# ltc3886_breadboardbreakout.net
KiCad netlist of a schematic drawn in EAGLE
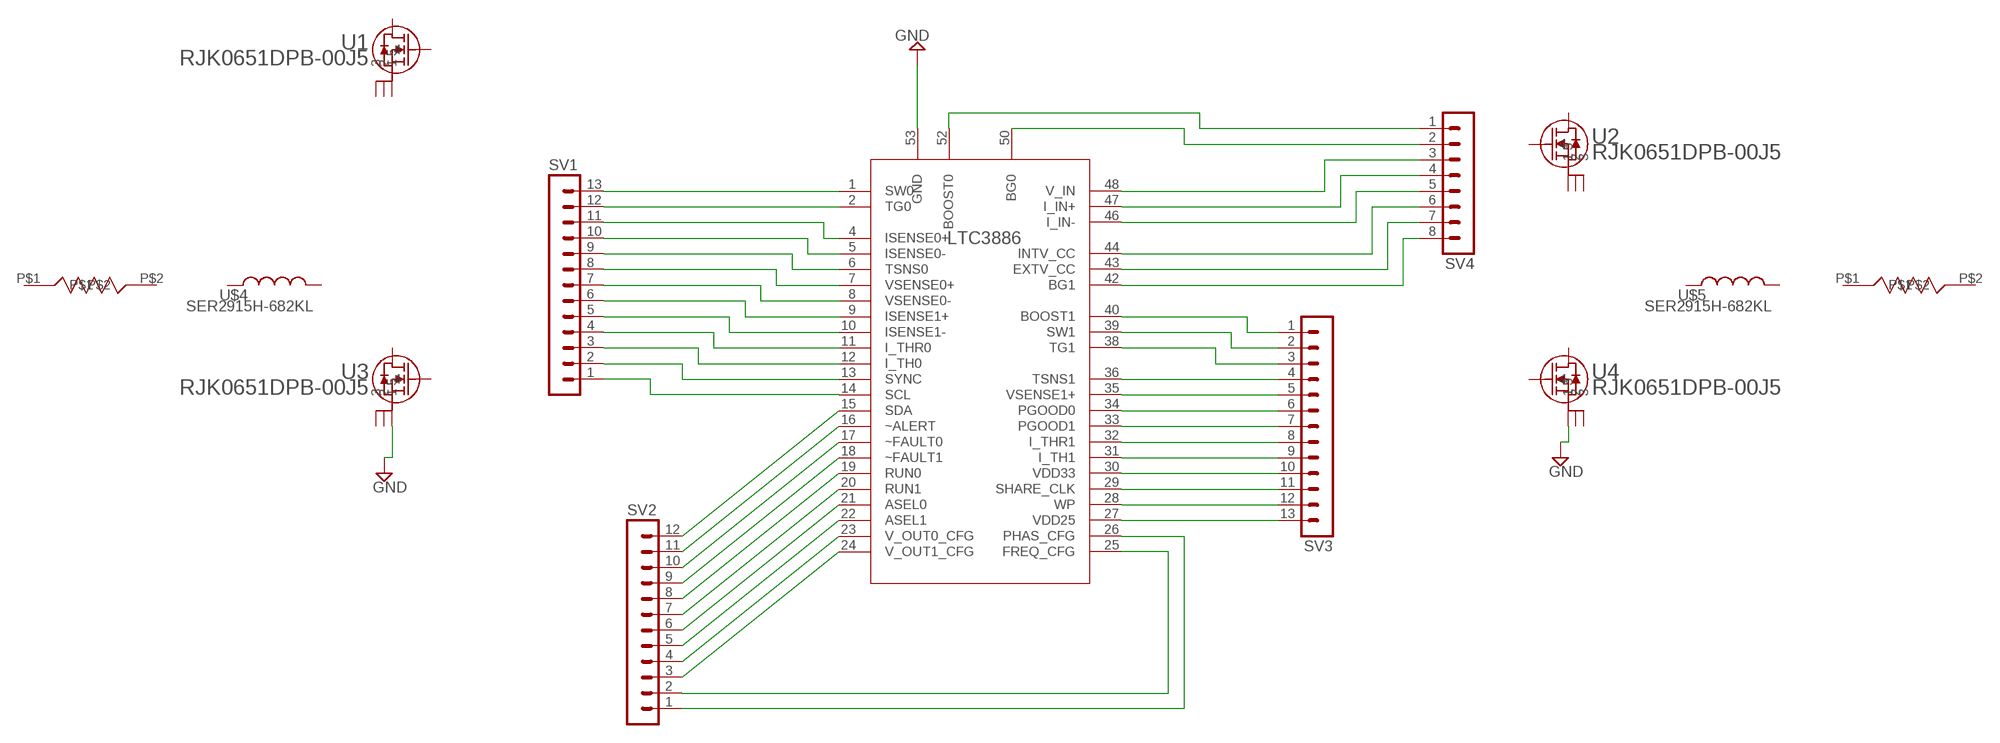
[diagram p0: schematic, sheet 1]

(export (version "E")
  (design (tool "Eeschema 10.0.6"))
  (components
    (comp (ref "GND")
      (value "LTC3886")
      (footprint "eagle-import:QFN-52_UKG_2")
      (libsource (lib "eagle-import") (part "LTC3886"))
    )
    (comp (ref "SV1")
      (value "MA13-1")
      (footprint "eagle-import:MA13-1")
      (libsource (lib "eagle-import") (part "MA13-1"))
    )
    (comp (ref "SV2")
      (value "MA12-1")
      (footprint "eagle-import:MA12-1")
      (libsource (lib "eagle-import") (part "MA12-1"))
    )
    (comp (ref "SV3")
      (value "MA13-1")
      (footprint "eagle-import:MA13-1")
      (libsource (lib "eagle-import") (part "MA13-1"))
    )
    (comp (ref "SV4")
      (value "MA08-1")
      (footprint "eagle-import:MA08-1")
      (libsource (lib "eagle-import") (part "MA08-1"))
    )
    (comp (ref "U$2")
      (value "CSS2H-2512K-2L00FE")
      (footprint "eagle-import:CSS2H-2512K-2L00FE")
      (libsource (lib "eagle-import") (part "CSS2H-2512K-2L00FE"))
    )
    (comp (ref "U$3")
      (value "CSS2H-2512K-2L00FE")
      (footprint "eagle-import:CSS2H-2512K-2L00FE")
      (libsource (lib "eagle-import") (part "CSS2H-2512K-2L00FE"))
    )
    (comp (ref "U$4")
      (value "SER2915H-682KL")
      (footprint "eagle-import:SER2915H-682KL")
      (libsource (lib "eagle-import") (part "SER2915H-682KL"))
    )
    (comp (ref "U$5")
      (value "SER2915H-682KL")
      (footprint "eagle-import:SER2915H-682KL")
      (libsource (lib "eagle-import") (part "SER2915H-682KL"))
    )
    (comp (ref "U1")
      (value "RJK0651DPB-00J5")
      (footprint "eagle-import:LFPAK")
      (fields (field (name "MANUFACTURER_PART_NUMBER") "RJK0651DPB00#J5"))
      (libsource (lib "eagle-import") (part "RJK0651DPB-00J5"))
    )
    (comp (ref "U2")
      (value "RJK0651DPB-00J5")
      (footprint "eagle-import:LFPAK")
      (fields (field (name "MANUFACTURER_PART_NUMBER") "RJK0651DPB00#J5"))
      (libsource (lib "eagle-import") (part "RJK0651DPB-00J5"))
    )
    (comp (ref "U3")
      (value "RJK0651DPB-00J5")
      (footprint "eagle-import:LFPAK")
      (fields (field (name "MANUFACTURER_PART_NUMBER") "RJK0651DPB00#J5"))
      (libsource (lib "eagle-import") (part "RJK0651DPB-00J5"))
    )
    (comp (ref "U4")
      (value "RJK0651DPB-00J5")
      (footprint "eagle-import:LFPAK")
      (fields (field (name "MANUFACTURER_PART_NUMBER") "RJK0651DPB00#J5"))
      (libsource (lib "eagle-import") (part "RJK0651DPB-00J5"))
    )
  )
  (nets
    (net (code "1") (name "GND") (class "Default")
      (node (ref "GND") (pin "53") (pinfunction "GND_53") (pintype "bidirectional"))
      (node (ref "U3") (pin "1") (pinfunction "1_1") (pintype "passive"))
      (node (ref "U4") (pin "1") (pinfunction "1_1") (pintype "passive"))
    )
    (net (code "2") (name "Net-(GND-ASEL0)") (class "Default")
      (node (ref "GND") (pin "21") (pinfunction "ASEL0_21") (pintype "passive"))
      (node (ref "SV2") (pin "6") (pinfunction "6_6") (pintype "passive"))
    )
    (net (code "3") (name "Net-(GND-ASEL1)") (class "Default")
      (node (ref "GND") (pin "22") (pinfunction "ASEL1_22") (pintype "passive"))
      (node (ref "SV2") (pin "5") (pinfunction "5_5") (pintype "passive"))
    )
    (net (code "4") (name "Net-(GND-BG0)") (class "Default")
      (node (ref "GND") (pin "50") (pinfunction "BG0_50") (pintype "bidirectional"))
      (node (ref "SV4") (pin "2") (pinfunction "2_2") (pintype "passive"))
    )
    (net (code "5") (name "Net-(GND-BG1)") (class "Default")
      (node (ref "GND") (pin "42") (pinfunction "BG1_42") (pintype "passive"))
      (node (ref "SV4") (pin "8") (pinfunction "8_8") (pintype "passive"))
    )
    (net (code "6") (name "Net-(GND-BOOST0)") (class "Default")
      (node (ref "GND") (pin "52") (pinfunction "BOOST0_52") (pintype "bidirectional"))
      (node (ref "SV4") (pin "1") (pinfunction "1_1") (pintype "passive"))
    )
    (net (code "7") (name "Net-(GND-BOOST1)") (class "Default")
      (node (ref "GND") (pin "40") (pinfunction "BOOST1_40") (pintype "passive"))
      (node (ref "SV3") (pin "1") (pinfunction "1_1") (pintype "passive"))
    )
    (net (code "8") (name "Net-(GND-EXTV_CC)") (class "Default")
      (node (ref "GND") (pin "43") (pinfunction "EXTV_CC_43") (pintype "passive"))
      (node (ref "SV4") (pin "7") (pinfunction "7_7") (pintype "passive"))
    )
    (net (code "9") (name "Net-(GND-FREQ_CFG)") (class "Default")
      (node (ref "GND") (pin "25") (pinfunction "FREQ_CFG_25") (pintype "passive"))
      (node (ref "SV2") (pin "2") (pinfunction "2_2") (pintype "passive"))
    )
    (net (code "10") (name "Net-(GND-INTV_CC)") (class "Default")
      (node (ref "GND") (pin "44") (pinfunction "INTV_CC_44") (pintype "passive"))
      (node (ref "SV4") (pin "6") (pinfunction "6_6") (pintype "passive"))
    )
    (net (code "11") (name "Net-(GND-ISENSE0+)") (class "Default")
      (node (ref "GND") (pin "4") (pinfunction "ISENSE0+_4") (pintype "passive"))
      (node (ref "SV1") (pin "11") (pinfunction "11_11") (pintype "passive"))
    )
    (net (code "12") (name "Net-(GND-ISENSE0-)") (class "Default")
      (node (ref "GND") (pin "5") (pinfunction "ISENSE0-_5") (pintype "passive"))
      (node (ref "SV1") (pin "10") (pinfunction "10_10") (pintype "passive"))
    )
    (net (code "13") (name "Net-(GND-ISENSE1+)") (class "Default")
      (node (ref "GND") (pin "9") (pinfunction "ISENSE1+_9") (pintype "passive"))
      (node (ref "SV1") (pin "6") (pinfunction "6_6") (pintype "passive"))
    )
    (net (code "14") (name "Net-(GND-ISENSE1-)") (class "Default")
      (node (ref "GND") (pin "10") (pinfunction "ISENSE1-_10") (pintype "passive"))
      (node (ref "SV1") (pin "5") (pinfunction "5_5") (pintype "passive"))
    )
    (net (code "15") (name "Net-(GND-I_IN+)") (class "Default")
      (node (ref "GND") (pin "47") (pinfunction "I_IN+_47") (pintype "passive"))
      (node (ref "SV4") (pin "4") (pinfunction "4_4") (pintype "passive"))
    )
    (net (code "16") (name "Net-(GND-I_IN-)") (class "Default")
      (node (ref "GND") (pin "46") (pinfunction "I_IN-_46") (pintype "passive"))
      (node (ref "SV4") (pin "5") (pinfunction "5_5") (pintype "passive"))
    )
    (net (code "17") (name "Net-(GND-I_TH0)") (class "Default")
      (node (ref "GND") (pin "12") (pinfunction "I_TH0_12") (pintype "passive"))
      (node (ref "SV1") (pin "3") (pinfunction "3_3") (pintype "passive"))
    )
    (net (code "18") (name "Net-(GND-I_TH1)") (class "Default")
      (node (ref "GND") (pin "31") (pinfunction "I_TH1_31") (pintype "passive"))
      (node (ref "SV3") (pin "9") (pinfunction "9_9") (pintype "passive"))
    )
    (net (code "19") (name "Net-(GND-I_THR0)") (class "Default")
      (node (ref "GND") (pin "11") (pinfunction "I_THR0_11") (pintype "passive"))
      (node (ref "SV1") (pin "4") (pinfunction "4_4") (pintype "passive"))
    )
    (net (code "20") (name "Net-(GND-I_THR1)") (class "Default")
      (node (ref "GND") (pin "32") (pinfunction "I_THR1_32") (pintype "passive"))
      (node (ref "SV3") (pin "8") (pinfunction "8_8") (pintype "passive"))
    )
    (net (code "21") (name "Net-(GND-PGOOD0)") (class "Default")
      (node (ref "GND") (pin "34") (pinfunction "PGOOD0_34") (pintype "passive"))
      (node (ref "SV3") (pin "6") (pinfunction "6_6") (pintype "passive"))
    )
    (net (code "22") (name "Net-(GND-PGOOD1)") (class "Default")
      (node (ref "GND") (pin "33") (pinfunction "PGOOD1_33") (pintype "passive"))
      (node (ref "SV3") (pin "7") (pinfunction "7_7") (pintype "passive"))
    )
    (net (code "23") (name "Net-(GND-PHAS_CFG)") (class "Default")
      (node (ref "GND") (pin "26") (pinfunction "PHAS_CFG_26") (pintype "passive"))
      (node (ref "SV2") (pin "1") (pinfunction "1_1") (pintype "passive"))
    )
    (net (code "24") (name "Net-(GND-RUN0)") (class "Default")
      (node (ref "GND") (pin "19") (pinfunction "RUN0_19") (pintype "passive"))
      (node (ref "SV2") (pin "8") (pinfunction "8_8") (pintype "passive"))
    )
    (net (code "25") (name "Net-(GND-RUN1)") (class "Default")
      (node (ref "GND") (pin "20") (pinfunction "RUN1_20") (pintype "passive"))
      (node (ref "SV2") (pin "7") (pinfunction "7_7") (pintype "passive"))
    )
    (net (code "26") (name "Net-(GND-SCL)") (class "Default")
      (node (ref "GND") (pin "14") (pinfunction "SCL_14") (pintype "passive"))
      (node (ref "SV1") (pin "1") (pinfunction "1_1") (pintype "passive"))
    )
    (net (code "27") (name "Net-(GND-SDA)") (class "Default")
      (node (ref "GND") (pin "15") (pinfunction "SDA_15") (pintype "passive"))
      (node (ref "SV2") (pin "12") (pinfunction "12_12") (pintype "passive"))
    )
    (net (code "28") (name "Net-(GND-SHARE_CLK)") (class "Default")
      (node (ref "GND") (pin "29") (pinfunction "SHARE_CLK_29") (pintype "passive"))
      (node (ref "SV3") (pin "11") (pinfunction "11_11") (pintype "passive"))
    )
    (net (code "29") (name "Net-(GND-SW0)") (class "Default")
      (node (ref "GND") (pin "1") (pinfunction "SW0_1") (pintype "passive"))
      (node (ref "SV1") (pin "13") (pinfunction "13_13") (pintype "passive"))
    )
    (net (code "30") (name "Net-(GND-SW1)") (class "Default")
      (node (ref "GND") (pin "39") (pinfunction "SW1_39") (pintype "passive"))
      (node (ref "SV3") (pin "2") (pinfunction "2_2") (pintype "passive"))
    )
    (net (code "31") (name "Net-(GND-SYNC)") (class "Default")
      (node (ref "GND") (pin "13") (pinfunction "SYNC_13") (pintype "passive"))
      (node (ref "SV1") (pin "2") (pinfunction "2_2") (pintype "passive"))
    )
    (net (code "32") (name "Net-(GND-TG0)") (class "Default")
      (node (ref "GND") (pin "2") (pinfunction "TG0_2") (pintype "passive"))
      (node (ref "SV1") (pin "12") (pinfunction "12_12") (pintype "passive"))
    )
    (net (code "33") (name "Net-(GND-TG1)") (class "Default")
      (node (ref "GND") (pin "38") (pinfunction "TG1_38") (pintype "passive"))
      (node (ref "SV3") (pin "3") (pinfunction "3_3") (pintype "passive"))
    )
    (net (code "34") (name "Net-(GND-TSNS0)") (class "Default")
      (node (ref "GND") (pin "6") (pinfunction "TSNS0_6") (pintype "passive"))
      (node (ref "SV1") (pin "9") (pinfunction "9_9") (pintype "passive"))
    )
    (net (code "35") (name "Net-(GND-TSNS1)") (class "Default")
      (node (ref "GND") (pin "36") (pinfunction "TSNS1_36") (pintype "passive"))
      (node (ref "SV3") (pin "4") (pinfunction "4_4") (pintype "passive"))
    )
    (net (code "36") (name "Net-(GND-VDD25)") (class "Default")
      (node (ref "GND") (pin "27") (pinfunction "VDD25_27") (pintype "passive"))
      (node (ref "SV3") (pin "13") (pinfunction "13_13") (pintype "passive"))
    )
    (net (code "37") (name "Net-(GND-VDD33)") (class "Default")
      (node (ref "GND") (pin "30") (pinfunction "VDD33_30") (pintype "passive"))
      (node (ref "SV3") (pin "10") (pinfunction "10_10") (pintype "passive"))
    )
    (net (code "38") (name "Net-(GND-VSENSE0+)") (class "Default")
      (node (ref "GND") (pin "7") (pinfunction "VSENSE0+_7") (pintype "passive"))
      (node (ref "SV1") (pin "8") (pinfunction "8_8") (pintype "passive"))
    )
    (net (code "39") (name "Net-(GND-VSENSE0-)") (class "Default")
      (node (ref "GND") (pin "8") (pinfunction "VSENSE0-_8") (pintype "passive"))
      (node (ref "SV1") (pin "7") (pinfunction "7_7") (pintype "passive"))
    )
    (net (code "40") (name "Net-(GND-VSENSE1+)") (class "Default")
      (node (ref "GND") (pin "35") (pinfunction "VSENSE1+_35") (pintype "passive"))
      (node (ref "SV3") (pin "5") (pinfunction "5_5") (pintype "passive"))
    )
    (net (code "41") (name "Net-(GND-V_IN)") (class "Default")
      (node (ref "GND") (pin "48") (pinfunction "V_IN_48") (pintype "passive"))
      (node (ref "SV4") (pin "3") (pinfunction "3_3") (pintype "passive"))
    )
    (net (code "42") (name "Net-(GND-V_OUT0_CFG)") (class "Default")
      (node (ref "GND") (pin "23") (pinfunction "V_OUT0_CFG_23") (pintype "passive"))
      (node (ref "SV2") (pin "4") (pinfunction "4_4") (pintype "passive"))
    )
    (net (code "43") (name "Net-(GND-V_OUT1_CFG)") (class "Default")
      (node (ref "GND") (pin "24") (pinfunction "V_OUT1_CFG_24") (pintype "passive"))
      (node (ref "SV2") (pin "3") (pinfunction "3_3") (pintype "passive"))
    )
    (net (code "44") (name "Net-(GND-WP)") (class "Default")
      (node (ref "GND") (pin "28") (pinfunction "WP_28") (pintype "passive"))
      (node (ref "SV3") (pin "12") (pinfunction "12_12") (pintype "passive"))
    )
    (net (code "45") (name "Net-(GND-~{ALERT})") (class "Default")
      (node (ref "GND") (pin "16") (pinfunction "~{ALERT}_16") (pintype "passive"))
      (node (ref "SV2") (pin "11") (pinfunction "11_11") (pintype "passive"))
    )
    (net (code "46") (name "Net-(GND-~{FAULT0})") (class "Default")
      (node (ref "GND") (pin "17") (pinfunction "~{FAULT0}_17") (pintype "passive"))
      (node (ref "SV2") (pin "10") (pinfunction "10_10") (pintype "passive"))
    )
    (net (code "47") (name "Net-(GND-~{FAULT1})") (class "Default")
      (node (ref "GND") (pin "18") (pinfunction "~{FAULT1}_18") (pintype "passive"))
      (node (ref "SV2") (pin "9") (pinfunction "9_9") (pintype "passive"))
    )
    (net (code "48") (name "unconnected-(U$2-PadP$1)") (class "Default")
      (node (ref "U$2") (pin "P$1") (pinfunction "P$1_P$1") (pintype "bidirectional"))
    )
    (net (code "49") (name "unconnected-(U$2-PadP$2)") (class "Default")
      (node (ref "U$2") (pin "P$2") (pinfunction "P$2_P$2") (pintype "bidirectional"))
    )
    (net (code "50") (name "unconnected-(U$3-PadP$1)") (class "Default")
      (node (ref "U$3") (pin "P$1") (pinfunction "P$1_P$1") (pintype "bidirectional"))
    )
    (net (code "51") (name "unconnected-(U$3-PadP$2)") (class "Default")
      (node (ref "U$3") (pin "P$2") (pinfunction "P$2_P$2") (pintype "bidirectional"))
    )
    (net (code "52") (name "unconnected-(U$4-1-PadP$1)") (class "Default")
      (node (ref "U$4") (pin "P$1") (pinfunction "1_P$1") (pintype "passive"))
    )
    (net (code "53") (name "unconnected-(U$4-2-PadP$2)") (class "Default")
      (node (ref "U$4") (pin "P$2") (pinfunction "2_P$2") (pintype "passive"))
    )
    (net (code "54") (name "unconnected-(U$5-1-PadP$1)") (class "Default")
      (node (ref "U$5") (pin "P$1") (pinfunction "1_P$1") (pintype "passive"))
    )
    (net (code "55") (name "unconnected-(U$5-2-PadP$2)") (class "Default")
      (node (ref "U$5") (pin "P$2") (pinfunction "2_P$2") (pintype "passive"))
    )
    (net (code "56") (name "unconnected-(U1-Pad1)") (class "Default")
      (node (ref "U1") (pin "1") (pinfunction "1_1") (pintype "passive"))
    )
    (net (code "57") (name "unconnected-(U1-Pad2)") (class "Default")
      (node (ref "U1") (pin "2") (pinfunction "2_2") (pintype "passive"))
    )
    (net (code "58") (name "unconnected-(U1-Pad3)") (class "Default")
      (node (ref "U1") (pin "3") (pinfunction "3_3") (pintype "passive"))
    )
    (net (code "59") (name "unconnected-(U1-Pad4)") (class "Default")
      (node (ref "U1") (pin "4") (pinfunction "4_4") (pintype "passive"))
    )
    (net (code "60") (name "unconnected-(U1-Pad5)") (class "Default")
      (node (ref "U1") (pin "5") (pinfunction "5_5") (pintype "passive"))
    )
    (net (code "61") (name "unconnected-(U2-Pad1)") (class "Default")
      (node (ref "U2") (pin "1") (pinfunction "1_1") (pintype "passive"))
    )
    (net (code "62") (name "unconnected-(U2-Pad2)") (class "Default")
      (node (ref "U2") (pin "2") (pinfunction "2_2") (pintype "passive"))
    )
    (net (code "63") (name "unconnected-(U2-Pad3)") (class "Default")
      (node (ref "U2") (pin "3") (pinfunction "3_3") (pintype "passive"))
    )
    (net (code "64") (name "unconnected-(U2-Pad4)") (class "Default")
      (node (ref "U2") (pin "4") (pinfunction "4_4") (pintype "passive"))
    )
    (net (code "65") (name "unconnected-(U2-Pad5)") (class "Default")
      (node (ref "U2") (pin "5") (pinfunction "5_5") (pintype "passive"))
    )
    (net (code "66") (name "unconnected-(U3-Pad2)") (class "Default")
      (node (ref "U3") (pin "2") (pinfunction "2_2") (pintype "passive"))
    )
    (net (code "67") (name "unconnected-(U3-Pad3)") (class "Default")
      (node (ref "U3") (pin "3") (pinfunction "3_3") (pintype "passive"))
    )
    (net (code "68") (name "unconnected-(U3-Pad4)") (class "Default")
      (node (ref "U3") (pin "4") (pinfunction "4_4") (pintype "passive"))
    )
    (net (code "69") (name "unconnected-(U3-Pad5)") (class "Default")
      (node (ref "U3") (pin "5") (pinfunction "5_5") (pintype "passive"))
    )
    (net (code "70") (name "unconnected-(U4-Pad2)") (class "Default")
      (node (ref "U4") (pin "2") (pinfunction "2_2") (pintype "passive"))
    )
    (net (code "71") (name "unconnected-(U4-Pad3)") (class "Default")
      (node (ref "U4") (pin "3") (pinfunction "3_3") (pintype "passive"))
    )
    (net (code "72") (name "unconnected-(U4-Pad4)") (class "Default")
      (node (ref "U4") (pin "4") (pinfunction "4_4") (pintype "passive"))
    )
    (net (code "73") (name "unconnected-(U4-Pad5)") (class "Default")
      (node (ref "U4") (pin "5") (pinfunction "5_5") (pintype "passive"))
    )
  )
)
